# schematics.net
KiCad netlist of a schematic drawn in EAGLE
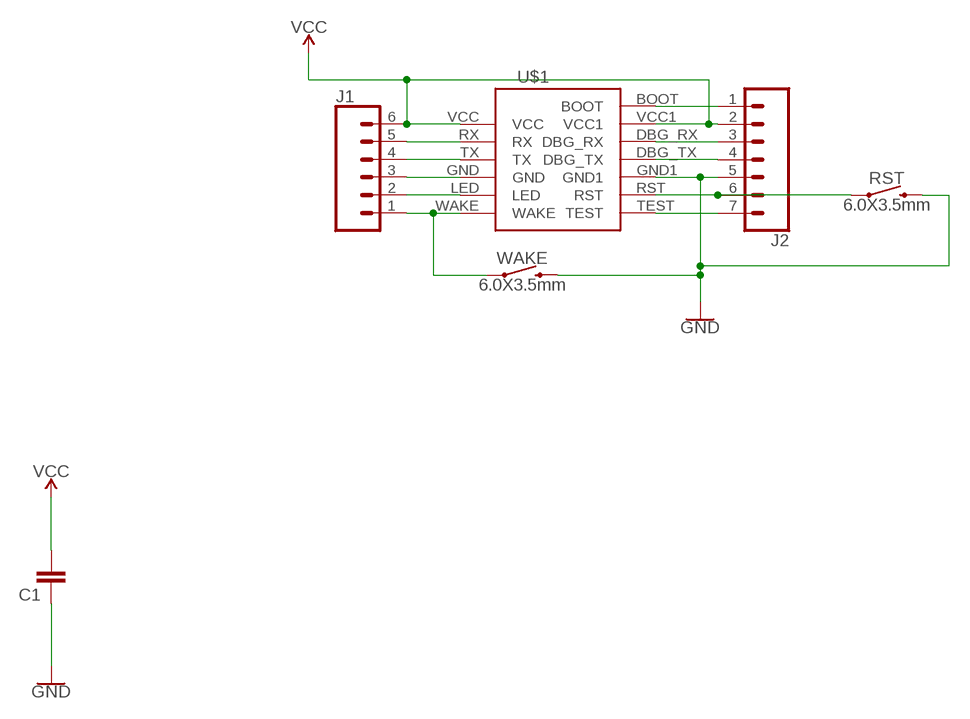
[diagram p0: schematic, sheet 1]

(export (version "E")
  (design (tool "Eeschema 10.0.6"))
  (components
    (comp (ref "C1")
      (value "C-EUC0805")
      (footprint "eagle-import:C0805")
      (libsource (lib "eagle-import") (part "C-EUC0805"))
    )
    (comp (ref "J1")
      (value "CONN_06LOCK")
      (footprint "eagle-import:1X06_LOCK")
      (libsource (lib "eagle-import") (part "CONN_06LOCK"))
    )
    (comp (ref "J2")
      (value "CONN_07LOCK")
      (footprint "eagle-import:1X07_LOCK")
      (libsource (lib "eagle-import") (part "CONN_07LOCK"))
    )
    (comp (ref "RST")
      (value "6.0X3.5mm")
      (footprint "eagle-import:TACTILE_SWITCH_SMD_6.0X3.5MM")
      (libsource (lib "eagle-import") (part "MOMENTARY-SWITCH-SPST-SMD-6.0X3.5MM"))
    )
    (comp (ref "U$1")
      (value "IM-L400")
      (footprint "eagle-import:IM-L400")
      (libsource (lib "eagle-import") (part "IM-L400"))
    )
    (comp (ref "WAKE")
      (value "6.0X3.5mm")
      (footprint "eagle-import:TACTILE_SWITCH_SMD_6.0X3.5MM")
      (libsource (lib "eagle-import") (part "MOMENTARY-SWITCH-SPST-SMD-6.0X3.5MM"))
    )
  )
  (nets
    (net (code "1") (name "GND") (class "Default")
      (node (ref "C1") (pin "1") (pinfunction "1_1") (pintype "passive"))
      (node (ref "J1") (pin "3") (pinfunction "3_3") (pintype "passive"))
      (node (ref "J2") (pin "5") (pinfunction "5_5") (pintype "passive"))
      (node (ref "RST") (pin "2") (pinfunction "2_2") (pintype "passive"))
      (node (ref "U$1") (pin "GND") (pinfunction "GND_GND") (pintype "bidirectional"))
      (node (ref "U$1") (pin "GND1") (pinfunction "GND1_GND1") (pintype "bidirectional"))
      (node (ref "WAKE") (pin "2") (pinfunction "2_2") (pintype "passive"))
    )
    (net (code "2") (name "Net-(J1-Pad1)") (class "Default")
      (node (ref "J1") (pin "1") (pinfunction "1_1") (pintype "passive"))
      (node (ref "U$1") (pin "WAKE") (pinfunction "WAKE_WAKE") (pintype "bidirectional"))
      (node (ref "WAKE") (pin "1") (pinfunction "1_1") (pintype "passive"))
    )
    (net (code "3") (name "Net-(J1-Pad2)") (class "Default")
      (node (ref "J1") (pin "2") (pinfunction "2_2") (pintype "passive"))
      (node (ref "U$1") (pin "LED") (pinfunction "LED_LED") (pintype "bidirectional"))
    )
    (net (code "4") (name "Net-(J1-Pad4)") (class "Default")
      (node (ref "J1") (pin "4") (pinfunction "4_4") (pintype "passive"))
      (node (ref "U$1") (pin "TX") (pinfunction "TX_TX") (pintype "bidirectional"))
    )
    (net (code "5") (name "Net-(J1-Pad5)") (class "Default")
      (node (ref "J1") (pin "5") (pinfunction "5_5") (pintype "passive"))
      (node (ref "U$1") (pin "RX") (pinfunction "RX_RX") (pintype "bidirectional"))
    )
    (net (code "6") (name "Net-(J2-Pad1)") (class "Default")
      (node (ref "J2") (pin "1") (pinfunction "1_1") (pintype "passive"))
      (node (ref "U$1") (pin "BOOT") (pinfunction "BOOT_BOOT") (pintype "bidirectional"))
    )
    (net (code "7") (name "Net-(J2-Pad3)") (class "Default")
      (node (ref "J2") (pin "3") (pinfunction "3_3") (pintype "passive"))
      (node (ref "U$1") (pin "DBG_RX") (pinfunction "DBG_RX_DBG_RX") (pintype "bidirectional"))
    )
    (net (code "8") (name "Net-(J2-Pad4)") (class "Default")
      (node (ref "J2") (pin "4") (pinfunction "4_4") (pintype "passive"))
      (node (ref "U$1") (pin "DBG_TX") (pinfunction "DBG_TX_DBG_TX") (pintype "bidirectional"))
    )
    (net (code "9") (name "Net-(J2-Pad6)") (class "Default")
      (node (ref "J2") (pin "6") (pinfunction "6_6") (pintype "passive"))
      (node (ref "RST") (pin "1") (pinfunction "1_1") (pintype "passive"))
      (node (ref "U$1") (pin "RST") (pinfunction "RST_RST") (pintype "bidirectional"))
    )
    (net (code "10") (name "Net-(J2-Pad7)") (class "Default")
      (node (ref "J2") (pin "7") (pinfunction "7_7") (pintype "passive"))
      (node (ref "U$1") (pin "TEST") (pinfunction "TEST_TEST") (pintype "bidirectional"))
    )
    (net (code "11") (name "VCC") (class "Default")
      (node (ref "C1") (pin "2") (pinfunction "2_2") (pintype "passive"))
      (node (ref "J1") (pin "6") (pinfunction "6_6") (pintype "passive"))
      (node (ref "J2") (pin "2") (pinfunction "2_2") (pintype "passive"))
      (node (ref "U$1") (pin "VCC") (pinfunction "VCC_VCC") (pintype "bidirectional"))
      (node (ref "U$1") (pin "VCC1") (pinfunction "VCC1_VCC1") (pintype "bidirectional"))
    )
  )
)
